# usbswitch_transistor1.net
KiCad netlist of a schematic drawn in EAGLE
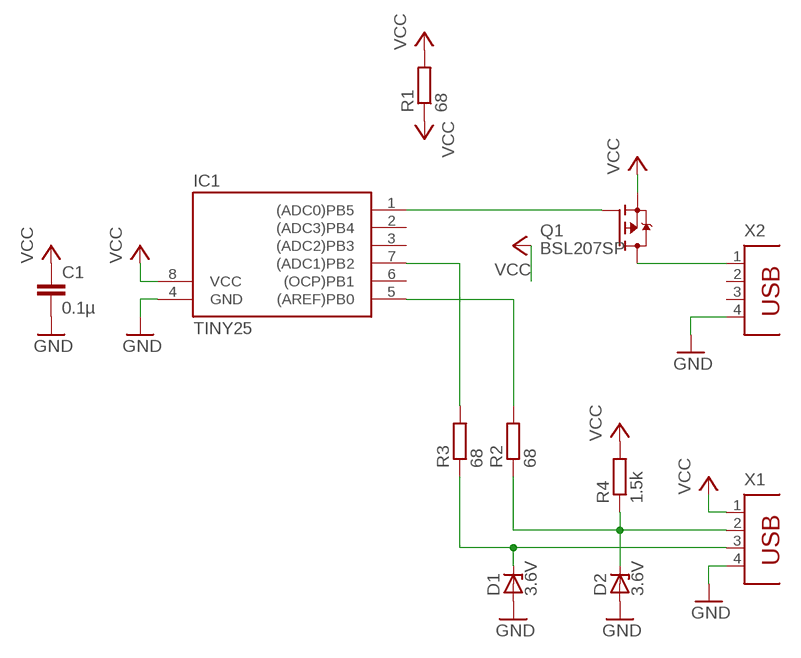
[diagram p0: schematic, sheet 1]

(export (version "E")
  (design (tool "Eeschema 10.0.6"))
  (components
    (comp (ref "C1")
      (value "0.1µ")
      (footprint "eagle-import:C1206")
      (libsource (lib "eagle-import") (part "C-EUC1206"))
    )
    (comp (ref "D1")
      (value "3.6V")
      (footprint "eagle-import:SOD80C")
      (libsource (lib "eagle-import") (part "ZENER-DIODESOD80C"))
    )
    (comp (ref "D2")
      (value "3.6V")
      (footprint "eagle-import:SOD80C")
      (libsource (lib "eagle-import") (part "ZENER-DIODESOD80C"))
    )
    (comp (ref "IC1")
      (value "TINY25")
      (footprint "eagle-import:SOIC8")
      (libsource (lib "eagle-import") (part "TINY15LS"))
    )
    (comp (ref "Q1")
      (value "BSL207SP")
      (footprint "eagle-import:SOT23")
      (libsource (lib "eagle-import") (part "BSL207SP"))
    )
    (comp (ref "R1")
      (value "68")
      (footprint "eagle-import:R1206")
      (libsource (lib "eagle-import") (part "R-EU_R1206"))
    )
    (comp (ref "R2")
      (value "68")
      (footprint "eagle-import:R0805")
      (libsource (lib "eagle-import") (part "R-EU_R0805"))
    )
    (comp (ref "R3")
      (value "68")
      (footprint "eagle-import:R0805")
      (libsource (lib "eagle-import") (part "R-EU_R0805"))
    )
    (comp (ref "R4")
      (value "1.5k")
      (footprint "eagle-import:R0805")
      (libsource (lib "eagle-import") (part "R-EU_R0805"))
    )
    (comp (ref "X1")
      (value "PN87520")
      (footprint "eagle-import:PN87520")
      (libsource (lib "eagle-import") (part "PN87520"))
    )
    (comp (ref "X2")
      (value "PN87520")
      (footprint "eagle-import:PN87520")
      (libsource (lib "eagle-import") (part "PN87520"))
    )
  )
  (nets
    (net (code "1") (name "GND") (class "Default")
      (node (ref "C1") (pin "2") (pinfunction "2_2") (pintype "passive"))
      (node (ref "D1") (pin "A") (pinfunction "A_A") (pintype "passive"))
      (node (ref "D2") (pin "A") (pinfunction "A_A") (pintype "passive"))
      (node (ref "IC1") (pin "4") (pinfunction "GND_4") (pintype "power_in"))
      (node (ref "X1") (pin "4") (pinfunction "4_4") (pintype "passive"))
      (node (ref "X2") (pin "4") (pinfunction "4_4") (pintype "passive"))
    )
    (net (code "2") (name "Net-(D1-PadC)") (class "Default")
      (node (ref "D1") (pin "C") (pinfunction "C_C") (pintype "passive"))
      (node (ref "R3") (pin "1") (pinfunction "1_1") (pintype "passive"))
      (node (ref "X1") (pin "3") (pinfunction "3_3") (pintype "passive"))
    )
    (net (code "3") (name "Net-(D2-PadC)") (class "Default")
      (node (ref "D2") (pin "C") (pinfunction "C_C") (pintype "passive"))
      (node (ref "R2") (pin "1") (pinfunction "1_1") (pintype "passive"))
      (node (ref "R4") (pin "1") (pinfunction "1_1") (pintype "passive"))
      (node (ref "X1") (pin "2") (pinfunction "2_2") (pintype "passive"))
    )
    (net (code "4") (name "Net-(IC1-(ADC0)PB5)") (class "Default")
      (node (ref "IC1") (pin "1") (pinfunction "(ADC0)PB5_1") (pintype "bidirectional"))
      (node (ref "Q1") (pin "1") (pinfunction "G_1") (pintype "passive"))
    )
    (net (code "5") (name "Net-(IC1-(ADC1)PB2)") (class "Default")
      (node (ref "IC1") (pin "7") (pinfunction "(ADC1)PB2_7") (pintype "bidirectional"))
      (node (ref "R3") (pin "2") (pinfunction "2_2") (pintype "passive"))
    )
    (net (code "6") (name "Net-(IC1-(AREF)PB0)") (class "Default")
      (node (ref "IC1") (pin "5") (pinfunction "(AREF)PB0_5") (pintype "bidirectional"))
      (node (ref "R2") (pin "2") (pinfunction "2_2") (pintype "passive"))
    )
    (net (code "7") (name "Net-(Q1-D)") (class "Default")
      (node (ref "Q1") (pin "3") (pinfunction "D_3") (pintype "passive"))
      (node (ref "X2") (pin "1") (pinfunction "1_1") (pintype "passive"))
    )
    (net (code "8") (name "VCC") (class "Default")
      (node (ref "C1") (pin "1") (pinfunction "1_1") (pintype "passive"))
      (node (ref "IC1") (pin "8") (pinfunction "VCC_8") (pintype "power_in"))
      (node (ref "Q1") (pin "2") (pinfunction "S_2") (pintype "passive"))
      (node (ref "R1") (pin "1") (pinfunction "1_1") (pintype "passive"))
      (node (ref "R1") (pin "2") (pinfunction "2_2") (pintype "passive"))
      (node (ref "R4") (pin "2") (pinfunction "2_2") (pintype "passive"))
      (node (ref "X1") (pin "1") (pinfunction "1_1") (pintype "passive"))
    )
    (net (code "9") (name "unconnected-(IC1-(ADC2)PB3-Pad3)") (class "Default")
      (node (ref "IC1") (pin "3") (pinfunction "(ADC2)PB3_3") (pintype "bidirectional"))
    )
    (net (code "10") (name "unconnected-(IC1-(ADC3)PB4-Pad2)") (class "Default")
      (node (ref "IC1") (pin "2") (pinfunction "(ADC3)PB4_2") (pintype "bidirectional"))
    )
    (net (code "11") (name "unconnected-(IC1-(OCP)PB1-Pad6)") (class "Default")
      (node (ref "IC1") (pin "6") (pinfunction "(OCP)PB1_6") (pintype "bidirectional"))
    )
    (net (code "12") (name "unconnected-(X2-Pad2)") (class "Default")
      (node (ref "X2") (pin "2") (pinfunction "2_2") (pintype "passive"))
    )
    (net (code "13") (name "unconnected-(X2-Pad3)") (class "Default")
      (node (ref "X2") (pin "3") (pinfunction "3_3") (pintype "passive"))
    )
  )
)
